# SNES2GP.net
KiCad netlist of a schematic drawn in EAGLE
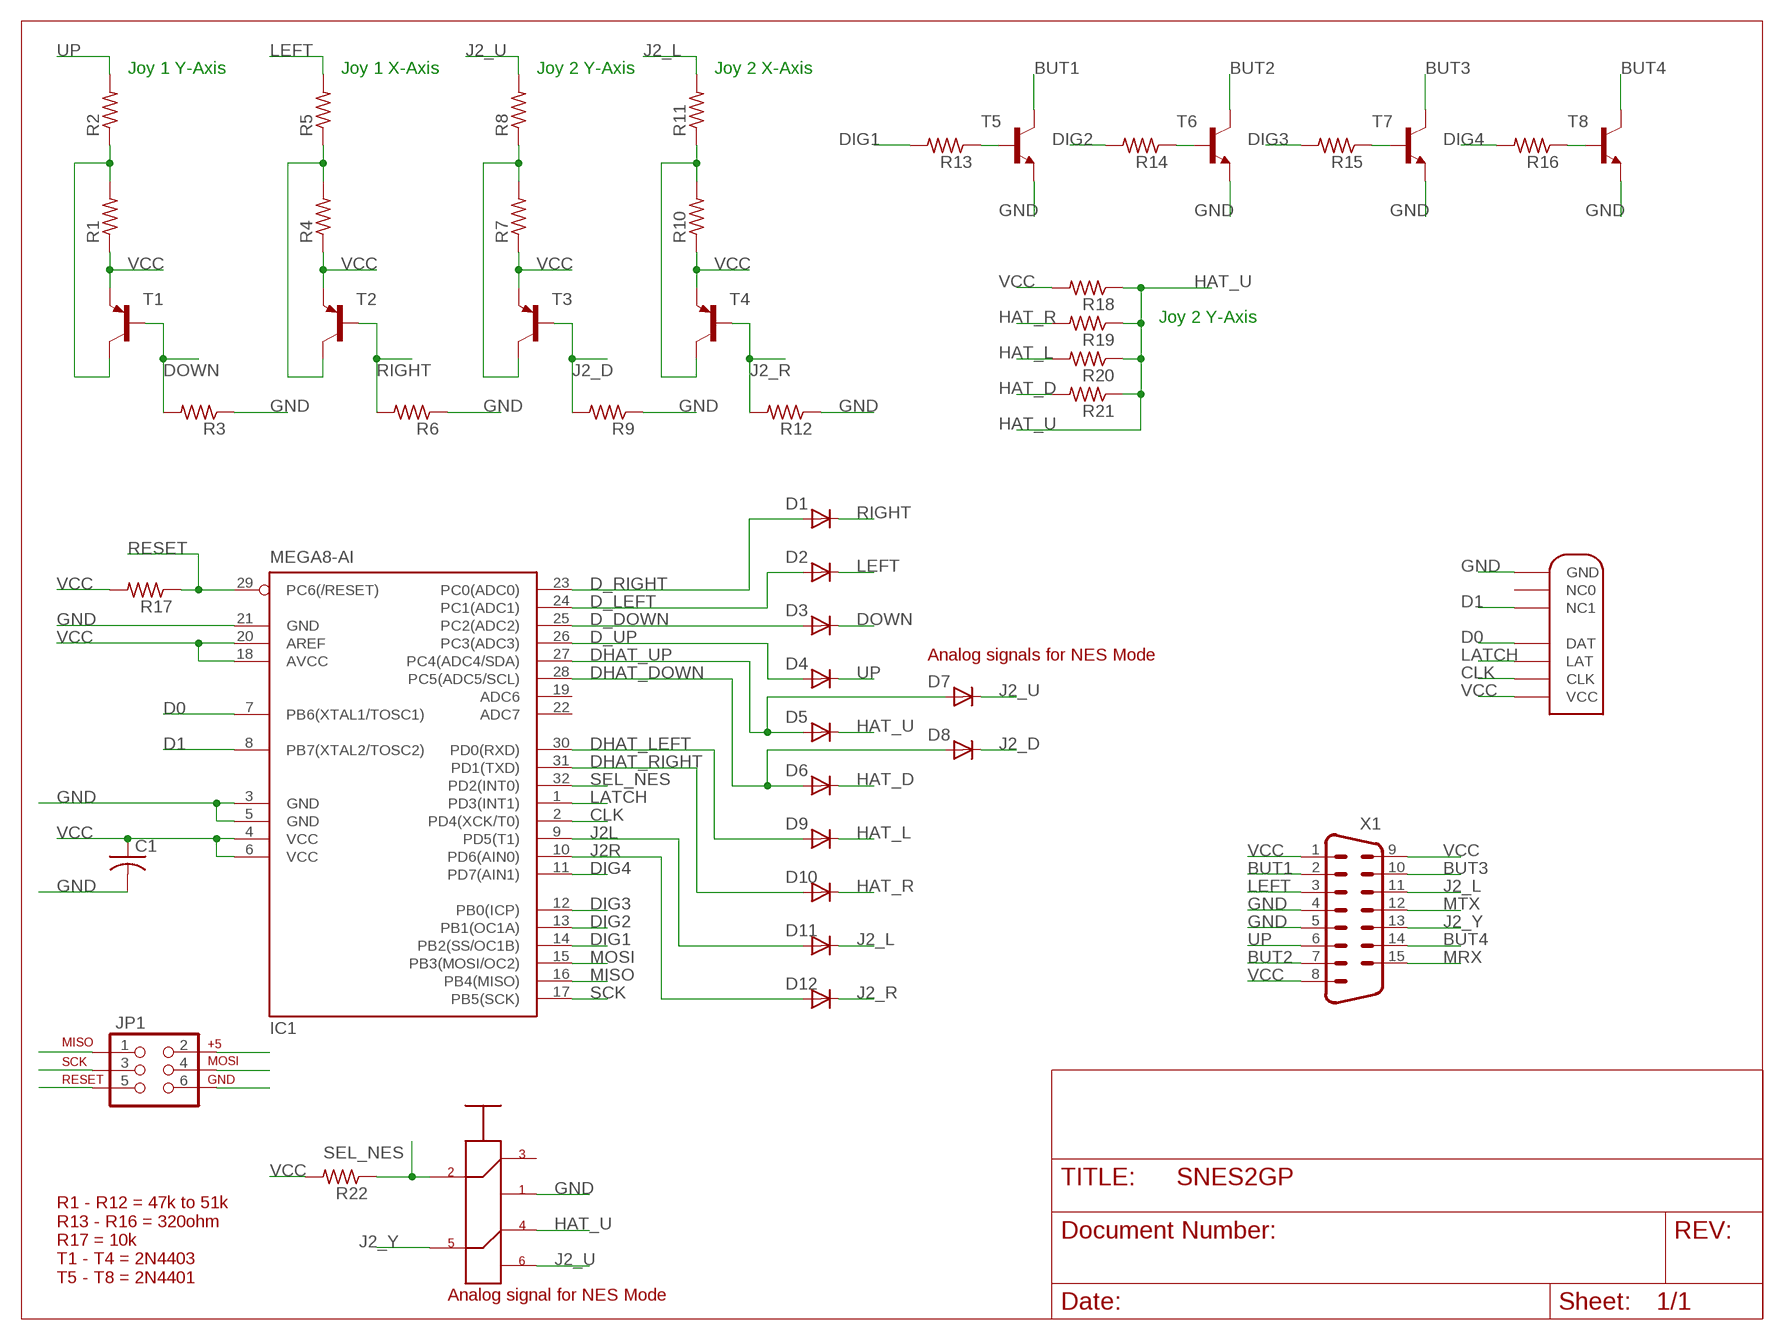
[diagram p0: schematic, sheet 1]

(export (version "E")
  (design (tool "Eeschema 10.0.6"))
  (components
    (comp (ref "C1")
      (value "C-USC0805")
      (footprint "eagle-import:C0805")
      (libsource (lib "eagle-import") (part "C-USC0805"))
    )
    (comp (ref "D1")
      (value "DIODE-SOD323-W")
      (footprint "eagle-import:SOD323-W")
      (libsource (lib "eagle-import") (part "DIODE-SOD323-W"))
    )
    (comp (ref "D2")
      (value "DIODE-SOD323-W")
      (footprint "eagle-import:SOD323-W")
      (libsource (lib "eagle-import") (part "DIODE-SOD323-W"))
    )
    (comp (ref "D3")
      (value "DIODE-SOD323-W")
      (footprint "eagle-import:SOD323-W")
      (libsource (lib "eagle-import") (part "DIODE-SOD323-W"))
    )
    (comp (ref "D4")
      (value "DIODE-SOD323-W")
      (footprint "eagle-import:SOD323-W")
      (libsource (lib "eagle-import") (part "DIODE-SOD323-W"))
    )
    (comp (ref "D5")
      (value "DIODE-SOD323-W")
      (footprint "eagle-import:SOD323-W")
      (libsource (lib "eagle-import") (part "DIODE-SOD323-W"))
    )
    (comp (ref "D6")
      (value "DIODE-SOD323-W")
      (footprint "eagle-import:SOD323-W")
      (libsource (lib "eagle-import") (part "DIODE-SOD323-W"))
    )
    (comp (ref "D7")
      (value "DIODE-SOD323-W")
      (footprint "eagle-import:SOD323-W")
      (libsource (lib "eagle-import") (part "DIODE-SOD323-W"))
    )
    (comp (ref "D8")
      (value "DIODE-SOD323-W")
      (footprint "eagle-import:SOD323-W")
      (libsource (lib "eagle-import") (part "DIODE-SOD323-W"))
    )
    (comp (ref "D9")
      (value "DIODE-SOD323-W")
      (footprint "eagle-import:SOD323-W")
      (libsource (lib "eagle-import") (part "DIODE-SOD323-W"))
    )
    (comp (ref "D10")
      (value "DIODE-SOD323-W")
      (footprint "eagle-import:SOD323-W")
      (libsource (lib "eagle-import") (part "DIODE-SOD323-W"))
    )
    (comp (ref "D11")
      (value "DIODE-SOD323-W")
      (footprint "eagle-import:SOD323-W")
      (libsource (lib "eagle-import") (part "DIODE-SOD323-W"))
    )
    (comp (ref "D12")
      (value "DIODE-SOD323-W")
      (footprint "eagle-import:SOD323-W")
      (libsource (lib "eagle-import") (part "DIODE-SOD323-W"))
    )
    (comp (ref "IC1")
      (value "MEGA8-AI")
      (footprint "eagle-import:TQFP32-08")
      (fields (field (name "MPN") "ATMEGA8-16AU"))
      (libsource (lib "eagle-import") (part "MEGA8-AI"))
    )
    (comp (ref "JP1")
      (value "AVR_SPI_PRG_6NS")
      (footprint "eagle-import:2X3-NS")
      (libsource (lib "eagle-import") (part "AVR_SPI_PRG_6NS"))
    )
    (comp (ref "R1")
      (value "R-US_M0805")
      (footprint "eagle-import:M0805")
      (libsource (lib "eagle-import") (part "R-US_M0805"))
    )
    (comp (ref "R2")
      (value "R-US_M0805")
      (footprint "eagle-import:M0805")
      (libsource (lib "eagle-import") (part "R-US_M0805"))
    )
    (comp (ref "R3")
      (value "R-US_M0805")
      (footprint "eagle-import:M0805")
      (libsource (lib "eagle-import") (part "R-US_M0805"))
    )
    (comp (ref "R4")
      (value "R-US_M0805")
      (footprint "eagle-import:M0805")
      (libsource (lib "eagle-import") (part "R-US_M0805"))
    )
    (comp (ref "R5")
      (value "R-US_M0805")
      (footprint "eagle-import:M0805")
      (libsource (lib "eagle-import") (part "R-US_M0805"))
    )
    (comp (ref "R6")
      (value "R-US_M0805")
      (footprint "eagle-import:M0805")
      (libsource (lib "eagle-import") (part "R-US_M0805"))
    )
    (comp (ref "R7")
      (value "R-US_M0805")
      (footprint "eagle-import:M0805")
      (libsource (lib "eagle-import") (part "R-US_M0805"))
    )
    (comp (ref "R8")
      (value "R-US_M0805")
      (footprint "eagle-import:M0805")
      (libsource (lib "eagle-import") (part "R-US_M0805"))
    )
    (comp (ref "R9")
      (value "R-US_M0805")
      (footprint "eagle-import:M0805")
      (libsource (lib "eagle-import") (part "R-US_M0805"))
    )
    (comp (ref "R10")
      (value "R-US_M0805")
      (footprint "eagle-import:M0805")
      (libsource (lib "eagle-import") (part "R-US_M0805"))
    )
    (comp (ref "R11")
      (value "R-US_M0805")
      (footprint "eagle-import:M0805")
      (libsource (lib "eagle-import") (part "R-US_M0805"))
    )
    (comp (ref "R12")
      (value "R-US_M0805")
      (footprint "eagle-import:M0805")
      (libsource (lib "eagle-import") (part "R-US_M0805"))
    )
    (comp (ref "R13")
      (value "R-US_M0805")
      (footprint "eagle-import:M0805")
      (libsource (lib "eagle-import") (part "R-US_M0805"))
    )
    (comp (ref "R14")
      (value "R-US_M0805")
      (footprint "eagle-import:M0805")
      (libsource (lib "eagle-import") (part "R-US_M0805"))
    )
    (comp (ref "R15")
      (value "R-US_M0805")
      (footprint "eagle-import:M0805")
      (libsource (lib "eagle-import") (part "R-US_M0805"))
    )
    (comp (ref "R16")
      (value "R-US_M0805")
      (footprint "eagle-import:M0805")
      (libsource (lib "eagle-import") (part "R-US_M0805"))
    )
    (comp (ref "R17")
      (value "R-US_M0805")
      (footprint "eagle-import:M0805")
      (libsource (lib "eagle-import") (part "R-US_M0805"))
    )
    (comp (ref "R18")
      (value "R-US_M0805")
      (footprint "eagle-import:M0805")
      (libsource (lib "eagle-import") (part "R-US_M0805"))
    )
    (comp (ref "R19")
      (value "R-US_M0805")
      (footprint "eagle-import:M0805")
      (libsource (lib "eagle-import") (part "R-US_M0805"))
    )
    (comp (ref "R20")
      (value "R-US_M0805")
      (footprint "eagle-import:M0805")
      (libsource (lib "eagle-import") (part "R-US_M0805"))
    )
    (comp (ref "R21")
      (value "R-US_M0805")
      (footprint "eagle-import:M0805")
      (libsource (lib "eagle-import") (part "R-US_M0805"))
    )
    (comp (ref "R22")
      (value "R-US_M0805")
      (footprint "eagle-import:M0805")
      (libsource (lib "eagle-import") (part "R-US_M0805"))
    )
    (comp (ref "T1")
      (value "MMBT3906")
      (footprint "eagle-import:SOT23")
      (libsource (lib "eagle-import") (part "MMBT3906"))
    )
    (comp (ref "T2")
      (value "MMBT3906")
      (footprint "eagle-import:SOT23")
      (libsource (lib "eagle-import") (part "MMBT3906"))
    )
    (comp (ref "T3")
      (value "MMBT3906")
      (footprint "eagle-import:SOT23")
      (libsource (lib "eagle-import") (part "MMBT3906"))
    )
    (comp (ref "T4")
      (value "MMBT3906")
      (footprint "eagle-import:SOT23")
      (libsource (lib "eagle-import") (part "MMBT3906"))
    )
    (comp (ref "T5")
      (value "MMBT3904")
      (footprint "eagle-import:SOT23")
      (libsource (lib "eagle-import") (part "MMBT3904"))
    )
    (comp (ref "T6")
      (value "MMBT3904")
      (footprint "eagle-import:SOT23")
      (libsource (lib "eagle-import") (part "MMBT3904"))
    )
    (comp (ref "T7")
      (value "MMBT3904")
      (footprint "eagle-import:SOT23")
      (libsource (lib "eagle-import") (part "MMBT3904"))
    )
    (comp (ref "T8")
      (value "MMBT3904")
      (footprint "eagle-import:SOT23")
      (libsource (lib "eagle-import") (part "MMBT3904"))
    )
    (comp (ref "U$1")
      (value "7X7_SW")
      (footprint "eagle-import:7X7_SW")
      (libsource (lib "eagle-import") (part "7X7_SW"))
    )
    (comp (ref "U$3")
      (value "SNES_GAMEPAD")
      (footprint "eagle-import:SNESCONN")
      (libsource (lib "eagle-import") (part "SNES_GAMEPAD"))
    )
    (comp (ref "X1")
      (value "M15HP")
      (footprint "eagle-import:M15HP")
      (libsource (lib "eagle-import") (part "M15HP"))
    )
  )
  (nets
    (net (code "1") (name "/BUT1") (class "Default")
      (node (ref "T5") (pin "3") (pinfunction "C_3") (pintype "passive"))
      (node (ref "X1") (pin "2") (pinfunction "2_2") (pintype "passive"))
    )
    (net (code "2") (name "/BUT2") (class "Default")
      (node (ref "T6") (pin "3") (pinfunction "C_3") (pintype "passive"))
      (node (ref "X1") (pin "7") (pinfunction "7_7") (pintype "passive"))
    )
    (net (code "3") (name "/BUT3") (class "Default")
      (node (ref "T7") (pin "3") (pinfunction "C_3") (pintype "passive"))
      (node (ref "X1") (pin "10") (pinfunction "10_10") (pintype "passive"))
    )
    (net (code "4") (name "/BUT4") (class "Default")
      (node (ref "T8") (pin "3") (pinfunction "C_3") (pintype "passive"))
      (node (ref "X1") (pin "14") (pinfunction "14_14") (pintype "passive"))
    )
    (net (code "5") (name "/CLK") (class "Default")
      (node (ref "IC1") (pin "2") (pinfunction "PD4(XCK/T0)_2") (pintype "bidirectional"))
      (node (ref "U$3") (pin "CLOCK") (pinfunction "CLK_CLOCK") (pintype "bidirectional"))
    )
    (net (code "6") (name "/D0") (class "Default")
      (node (ref "IC1") (pin "7") (pinfunction "PB6(XTAL1/TOSC1)_7") (pintype "bidirectional"))
      (node (ref "U$3") (pin "DATA") (pinfunction "DAT_DATA") (pintype "bidirectional"))
    )
    (net (code "7") (name "/D1") (class "Default")
      (node (ref "IC1") (pin "8") (pinfunction "PB7(XTAL2/TOSC2)_8") (pintype "bidirectional"))
      (node (ref "U$3") (pin "NC.") (pinfunction "NC1_NC.") (pintype "bidirectional"))
    )
    (net (code "8") (name "/DHAT_DOWN") (class "Default")
      (node (ref "D6") (pin "A") (pinfunction "A_A") (pintype "passive"))
      (node (ref "D8") (pin "A") (pinfunction "A_A") (pintype "passive"))
      (node (ref "IC1") (pin "28") (pinfunction "PC5(ADC5/SCL)_28") (pintype "bidirectional"))
    )
    (net (code "9") (name "/DHAT_LEFT") (class "Default")
      (node (ref "D9") (pin "A") (pinfunction "A_A") (pintype "passive"))
      (node (ref "IC1") (pin "30") (pinfunction "PD0(RXD)_30") (pintype "bidirectional"))
    )
    (net (code "10") (name "/DHAT_RIGHT") (class "Default")
      (node (ref "D10") (pin "A") (pinfunction "A_A") (pintype "passive"))
      (node (ref "IC1") (pin "31") (pinfunction "PD1(TXD)_31") (pintype "bidirectional"))
    )
    (net (code "11") (name "/DHAT_UP") (class "Default")
      (node (ref "D5") (pin "A") (pinfunction "A_A") (pintype "passive"))
      (node (ref "D7") (pin "A") (pinfunction "A_A") (pintype "passive"))
      (node (ref "IC1") (pin "27") (pinfunction "PC4(ADC4/SDA)_27") (pintype "bidirectional"))
    )
    (net (code "12") (name "/DIG1") (class "Default")
      (node (ref "IC1") (pin "14") (pinfunction "PB2(SS/OC1B)_14") (pintype "bidirectional"))
      (node (ref "R13") (pin "2") (pinfunction "2_2") (pintype "passive"))
    )
    (net (code "13") (name "/DIG2") (class "Default")
      (node (ref "IC1") (pin "13") (pinfunction "PB1(OC1A)_13") (pintype "bidirectional"))
      (node (ref "R14") (pin "2") (pinfunction "2_2") (pintype "passive"))
    )
    (net (code "14") (name "/DIG3") (class "Default")
      (node (ref "IC1") (pin "12") (pinfunction "PB0(ICP)_12") (pintype "bidirectional"))
      (node (ref "R15") (pin "2") (pinfunction "2_2") (pintype "passive"))
    )
    (net (code "15") (name "/DIG4") (class "Default")
      (node (ref "IC1") (pin "11") (pinfunction "PD7(AIN1)_11") (pintype "bidirectional"))
      (node (ref "R16") (pin "2") (pinfunction "2_2") (pintype "passive"))
    )
    (net (code "16") (name "/DOWN") (class "Default")
      (node (ref "D3") (pin "C") (pinfunction "C_C") (pintype "passive"))
      (node (ref "R3") (pin "2") (pinfunction "2_2") (pintype "passive"))
      (node (ref "T1") (pin "1") (pinfunction "B_1") (pintype "passive"))
    )
    (net (code "17") (name "/D_DOWN") (class "Default")
      (node (ref "D3") (pin "A") (pinfunction "A_A") (pintype "passive"))
      (node (ref "IC1") (pin "25") (pinfunction "PC2(ADC2)_25") (pintype "bidirectional"))
    )
    (net (code "18") (name "/D_LEFT") (class "Default")
      (node (ref "D2") (pin "A") (pinfunction "A_A") (pintype "passive"))
      (node (ref "IC1") (pin "24") (pinfunction "PC1(ADC1)_24") (pintype "bidirectional"))
    )
    (net (code "19") (name "/D_RIGHT") (class "Default")
      (node (ref "D1") (pin "A") (pinfunction "A_A") (pintype "passive"))
      (node (ref "IC1") (pin "23") (pinfunction "PC0(ADC0)_23") (pintype "bidirectional"))
    )
    (net (code "20") (name "/D_UP") (class "Default")
      (node (ref "D4") (pin "A") (pinfunction "A_A") (pintype "passive"))
      (node (ref "IC1") (pin "26") (pinfunction "PC3(ADC3)_26") (pintype "bidirectional"))
    )
    (net (code "21") (name "/GND") (class "Default")
      (node (ref "C1") (pin "2") (pinfunction "2_2") (pintype "passive"))
      (node (ref "IC1") (pin "21") (pinfunction "GND_21") (pintype "power_in"))
      (node (ref "IC1") (pin "3") (pinfunction "GND_3") (pintype "power_in"))
      (node (ref "IC1") (pin "5") (pinfunction "GND_5") (pintype "power_in"))
      (node (ref "JP1") (pin "6") (pinfunction "6_6") (pintype "passive"))
      (node (ref "R12") (pin "1") (pinfunction "1_1") (pintype "passive"))
      (node (ref "R3") (pin "1") (pinfunction "1_1") (pintype "passive"))
      (node (ref "R6") (pin "1") (pinfunction "1_1") (pintype "passive"))
      (node (ref "R9") (pin "1") (pinfunction "1_1") (pintype "passive"))
      (node (ref "T5") (pin "2") (pinfunction "E_2") (pintype "passive"))
      (node (ref "T6") (pin "2") (pinfunction "E_2") (pintype "passive"))
      (node (ref "T7") (pin "2") (pinfunction "E_2") (pintype "passive"))
      (node (ref "T8") (pin "2") (pinfunction "E_2") (pintype "passive"))
      (node (ref "U$1") (pin "P$1") (pinfunction "1_P$1") (pintype "bidirectional"))
      (node (ref "U$3") (pin "GND") (pinfunction "GND_GND") (pintype "bidirectional"))
      (node (ref "X1") (pin "4") (pinfunction "4_4") (pintype "passive"))
      (node (ref "X1") (pin "5") (pinfunction "5_5") (pintype "passive"))
    )
    (net (code "22") (name "/HAT_D") (class "Default")
      (node (ref "D6") (pin "C") (pinfunction "C_C") (pintype "passive"))
      (node (ref "R21") (pin "2") (pinfunction "2_2") (pintype "passive"))
    )
    (net (code "23") (name "/HAT_L") (class "Default")
      (node (ref "D9") (pin "C") (pinfunction "C_C") (pintype "passive"))
      (node (ref "R20") (pin "2") (pinfunction "2_2") (pintype "passive"))
    )
    (net (code "24") (name "/HAT_R") (class "Default")
      (node (ref "D10") (pin "C") (pinfunction "C_C") (pintype "passive"))
      (node (ref "R19") (pin "2") (pinfunction "2_2") (pintype "passive"))
    )
    (net (code "25") (name "/HAT_U") (class "Default")
      (node (ref "D5") (pin "C") (pinfunction "C_C") (pintype "passive"))
      (node (ref "R18") (pin "1") (pinfunction "1_1") (pintype "passive"))
      (node (ref "R19") (pin "1") (pinfunction "1_1") (pintype "passive"))
      (node (ref "R20") (pin "1") (pinfunction "1_1") (pintype "passive"))
      (node (ref "R21") (pin "1") (pinfunction "1_1") (pintype "passive"))
      (node (ref "U$1") (pin "P$4") (pinfunction "4_P$4") (pintype "bidirectional"))
    )
    (net (code "26") (name "/J2L") (class "Default")
      (node (ref "D11") (pin "A") (pinfunction "A_A") (pintype "passive"))
      (node (ref "IC1") (pin "9") (pinfunction "PD5(T1)_9") (pintype "bidirectional"))
    )
    (net (code "27") (name "/J2R") (class "Default")
      (node (ref "D12") (pin "A") (pinfunction "A_A") (pintype "passive"))
      (node (ref "IC1") (pin "10") (pinfunction "PD6(AIN0)_10") (pintype "bidirectional"))
    )
    (net (code "28") (name "/J2_D") (class "Default")
      (node (ref "D8") (pin "C") (pinfunction "C_C") (pintype "passive"))
      (node (ref "R9") (pin "2") (pinfunction "2_2") (pintype "passive"))
      (node (ref "T3") (pin "1") (pinfunction "B_1") (pintype "passive"))
    )
    (net (code "29") (name "/J2_L") (class "Default")
      (node (ref "D11") (pin "C") (pinfunction "C_C") (pintype "passive"))
      (node (ref "R11") (pin "2") (pinfunction "2_2") (pintype "passive"))
      (node (ref "X1") (pin "11") (pinfunction "11_11") (pintype "passive"))
    )
    (net (code "30") (name "/J2_R") (class "Default")
      (node (ref "D12") (pin "C") (pinfunction "C_C") (pintype "passive"))
      (node (ref "R12") (pin "2") (pinfunction "2_2") (pintype "passive"))
      (node (ref "T4") (pin "1") (pinfunction "B_1") (pintype "passive"))
    )
    (net (code "31") (name "/J2_U") (class "Default")
      (node (ref "D7") (pin "C") (pinfunction "C_C") (pintype "passive"))
      (node (ref "R8") (pin "2") (pinfunction "2_2") (pintype "passive"))
      (node (ref "U$1") (pin "P$6") (pinfunction "6_P$6") (pintype "bidirectional"))
    )
    (net (code "32") (name "/J2_Y") (class "Default")
      (node (ref "U$1") (pin "P$5") (pinfunction "5_P$5") (pintype "bidirectional"))
      (node (ref "X1") (pin "13") (pinfunction "13_13") (pintype "passive"))
    )
    (net (code "33") (name "/LATCH") (class "Default")
      (node (ref "IC1") (pin "1") (pinfunction "PD3(INT1)_1") (pintype "bidirectional"))
      (node (ref "U$3") (pin "LATCH") (pinfunction "LAT_LATCH") (pintype "bidirectional"))
    )
    (net (code "34") (name "/LEFT") (class "Default")
      (node (ref "D2") (pin "C") (pinfunction "C_C") (pintype "passive"))
      (node (ref "R5") (pin "2") (pinfunction "2_2") (pintype "passive"))
      (node (ref "X1") (pin "3") (pinfunction "3_3") (pintype "passive"))
    )
    (net (code "35") (name "/MISO") (class "Default")
      (node (ref "IC1") (pin "16") (pinfunction "PB4(MISO)_16") (pintype "bidirectional"))
      (node (ref "JP1") (pin "1") (pinfunction "1_1") (pintype "passive"))
    )
    (net (code "36") (name "/MOSI") (class "Default")
      (node (ref "IC1") (pin "15") (pinfunction "PB3(MOSI/OC2)_15") (pintype "bidirectional"))
      (node (ref "JP1") (pin "4") (pinfunction "4_4") (pintype "passive"))
    )
    (net (code "37") (name "/MRX") (class "Default")
      (node (ref "X1") (pin "15") (pinfunction "15_15") (pintype "passive"))
    )
    (net (code "38") (name "/MTX") (class "Default")
      (node (ref "X1") (pin "12") (pinfunction "12_12") (pintype "passive"))
    )
    (net (code "39") (name "/RESET") (class "Default")
      (node (ref "IC1") (pin "29") (pinfunction "PC6(/RESET)_29") (pintype "bidirectional"))
      (node (ref "JP1") (pin "5") (pinfunction "5_5") (pintype "passive"))
      (node (ref "R17") (pin "1") (pinfunction "1_1") (pintype "passive"))
    )
    (net (code "40") (name "/RIGHT") (class "Default")
      (node (ref "D1") (pin "C") (pinfunction "C_C") (pintype "passive"))
      (node (ref "R6") (pin "2") (pinfunction "2_2") (pintype "passive"))
      (node (ref "T2") (pin "1") (pinfunction "B_1") (pintype "passive"))
    )
    (net (code "41") (name "/SCK") (class "Default")
      (node (ref "IC1") (pin "17") (pinfunction "PB5(SCK)_17") (pintype "bidirectional"))
      (node (ref "JP1") (pin "3") (pinfunction "3_3") (pintype "passive"))
    )
    (net (code "42") (name "/SEL_NES") (class "Default")
      (node (ref "IC1") (pin "32") (pinfunction "PD2(INT0)_32") (pintype "bidirectional"))
      (node (ref "R22") (pin "1") (pinfunction "1_1") (pintype "passive"))
      (node (ref "U$1") (pin "P$2") (pinfunction "2_P$2") (pintype "bidirectional"))
    )
    (net (code "43") (name "/UP") (class "Default")
      (node (ref "D4") (pin "C") (pinfunction "C_C") (pintype "passive"))
      (node (ref "R2") (pin "2") (pinfunction "2_2") (pintype "passive"))
      (node (ref "X1") (pin "6") (pinfunction "6_6") (pintype "passive"))
    )
    (net (code "44") (name "/VCC") (class "Default")
      (node (ref "C1") (pin "1") (pinfunction "1_1") (pintype "passive"))
      (node (ref "IC1") (pin "18") (pinfunction "AVCC_18") (pintype "power_in"))
      (node (ref "IC1") (pin "20") (pinfunction "AREF_20") (pintype "passive"))
      (node (ref "IC1") (pin "4") (pinfunction "VCC_4") (pintype "power_in"))
      (node (ref "IC1") (pin "6") (pinfunction "VCC_6") (pintype "power_in"))
      (node (ref "JP1") (pin "2") (pinfunction "2_2") (pintype "passive"))
      (node (ref "R1") (pin "1") (pinfunction "1_1") (pintype "passive"))
      (node (ref "R10") (pin "1") (pinfunction "1_1") (pintype "passive"))
      (node (ref "R17") (pin "2") (pinfunction "2_2") (pintype "passive"))
      (node (ref "R18") (pin "2") (pinfunction "2_2") (pintype "passive"))
      (node (ref "R22") (pin "2") (pinfunction "2_2") (pintype "passive"))
      (node (ref "R4") (pin "1") (pinfunction "1_1") (pintype "passive"))
      (node (ref "R7") (pin "1") (pinfunction "1_1") (pintype "passive"))
      (node (ref "T1") (pin "2") (pinfunction "E_2") (pintype "passive"))
      (node (ref "T2") (pin "2") (pinfunction "E_2") (pintype "passive"))
      (node (ref "T3") (pin "2") (pinfunction "E_2") (pintype "passive"))
      (node (ref "T4") (pin "2") (pinfunction "E_2") (pintype "passive"))
      (node (ref "U$3") (pin "5V") (pinfunction "VCC_5V") (pintype "bidirectional"))
      (node (ref "X1") (pin "1") (pinfunction "1_1") (pintype "passive"))
      (node (ref "X1") (pin "8") (pinfunction "8_8") (pintype "passive"))
      (node (ref "X1") (pin "9") (pinfunction "9_9") (pintype "passive"))
    )
    (net (code "45") (name "Net-(T1-C)") (class "Default")
      (node (ref "R1") (pin "2") (pinfunction "2_2") (pintype "passive"))
      (node (ref "R2") (pin "1") (pinfunction "1_1") (pintype "passive"))
      (node (ref "T1") (pin "3") (pinfunction "C_3") (pintype "passive"))
    )
    (net (code "46") (name "Net-(T2-C)") (class "Default")
      (node (ref "R4") (pin "2") (pinfunction "2_2") (pintype "passive"))
      (node (ref "R5") (pin "1") (pinfunction "1_1") (pintype "passive"))
      (node (ref "T2") (pin "3") (pinfunction "C_3") (pintype "passive"))
    )
    (net (code "47") (name "Net-(T3-C)") (class "Default")
      (node (ref "R7") (pin "2") (pinfunction "2_2") (pintype "passive"))
      (node (ref "R8") (pin "1") (pinfunction "1_1") (pintype "passive"))
      (node (ref "T3") (pin "3") (pinfunction "C_3") (pintype "passive"))
    )
    (net (code "48") (name "Net-(T4-C)") (class "Default")
      (node (ref "R10") (pin "2") (pinfunction "2_2") (pintype "passive"))
      (node (ref "R11") (pin "1") (pinfunction "1_1") (pintype "passive"))
      (node (ref "T4") (pin "3") (pinfunction "C_3") (pintype "passive"))
    )
    (net (code "49") (name "Net-(T5-B)") (class "Default")
      (node (ref "R13") (pin "1") (pinfunction "1_1") (pintype "passive"))
      (node (ref "T5") (pin "1") (pinfunction "B_1") (pintype "passive"))
    )
    (net (code "50") (name "Net-(T6-B)") (class "Default")
      (node (ref "R14") (pin "1") (pinfunction "1_1") (pintype "passive"))
      (node (ref "T6") (pin "1") (pinfunction "B_1") (pintype "passive"))
    )
    (net (code "51") (name "Net-(T7-B)") (class "Default")
      (node (ref "R15") (pin "1") (pinfunction "1_1") (pintype "passive"))
      (node (ref "T7") (pin "1") (pinfunction "B_1") (pintype "passive"))
    )
    (net (code "52") (name "Net-(T8-B)") (class "Default")
      (node (ref "R16") (pin "1") (pinfunction "1_1") (pintype "passive"))
      (node (ref "T8") (pin "1") (pinfunction "B_1") (pintype "passive"))
    )
    (net (code "53") (name "unconnected-(IC1-ADC6-Pad19)") (class "Default")
      (node (ref "IC1") (pin "19") (pinfunction "ADC6_19") (pintype "bidirectional"))
    )
    (net (code "54") (name "unconnected-(IC1-ADC7-Pad22)") (class "Default")
      (node (ref "IC1") (pin "22") (pinfunction "ADC7_22") (pintype "bidirectional"))
    )
    (net (code "55") (name "unconnected-(U$1-3-PadP$3)") (class "Default")
      (node (ref "U$1") (pin "P$3") (pinfunction "3_P$3") (pintype "bidirectional"))
    )
    (net (code "56") (name "unconnected-(U$3-NC0-PadNC)") (class "Default")
      (node (ref "U$3") (pin "NC") (pinfunction "NC0_NC") (pintype "bidirectional"))
    )
  )
)
